# Heater_Driver.net
KiCad netlist of a schematic drawn in Altium Designer
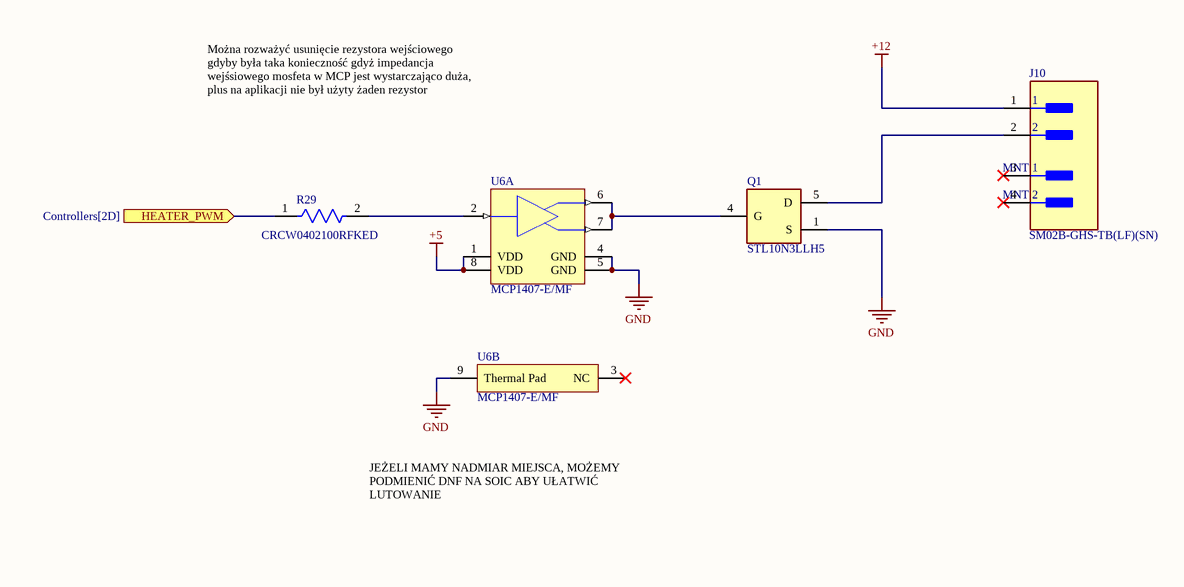
[diagram p0: Heater_Driver.SchDoc]

(export (version "E")
  (design (tool "Eeschema 10.0.6"))
  (components
    (comp (ref "J10")
      (value "SM02B-GHS-TB(LF)(SN)")
      (footprint "FP-SM02B-GHS-TB_LF_SN-MFG")
      (description "CONN HEADER SMD R/A 2POS 1.25MM")
      (libsource (lib "Altium Content Vault") (part "56ec3178a87b3978bdc1b3682cd516a"))
    )
    (comp (ref "Q1")
      (value "STL10N3LLH5")
      (footprint "STL10N3LLH5")
      (description "STMICROELECTRONICS - STL10N3LLH5 - MOSFET, N-CH, 30V, 9A, POWERFLAT")
      (fields (field (name "MOUSER PART NUMBER") "511-STL10N3LLH5"))
      (libsource (lib "STL10N3LLH5") (part "STL10N3LLH5"))
    )
    (comp (ref "R29")
      (value "CRCW0402100RFKED")
      (footprint "FP-CRCW0402-e3-IPC_C")
      (description "RES Thick Film, 100Ω, 1%, 0.063W, 100ppm/°C, 0402")
      (fields (field (name "TOLERANCE") "1%"))
      (libsource (lib "Altium Content Vault") (part "1029c3af85768c4190bb7ad29bc67b5"))
    )
    (comp (ref "U6")
      (value "MCP1407-E/MF")
      (footprint "DFNS-MF8")
      (description "6A High-Speed Power MOSFET Drivers, Non Inverting, Extended Temperature")
      (libsource (lib "Altium Content Vault") (part "IN-MOSDRV-TC4420-9"))
    )
  )
  (nets
    (net (code "1") (name "+5") (class "Default")
      (node (ref "U6") (pin "1") (pinfunction "VDD_1") (pintype "power_in"))
      (node (ref "U6") (pin "8") (pinfunction "VDD_8") (pintype "power_in"))
    )
    (net (code "2") (name "+12") (class "Default")
      (node (ref "J10") (pin "1") (pinfunction "1_1") (pintype "passive"))
    )
    (net (code "3") (name "/HEATER_PWM") (class "Default")
      (node (ref "R29") (pin "1") (pinfunction "1_1") (pintype "passive"))
    )
    (net (code "4") (name "GND") (class "Default")
      (node (ref "Q1") (pin "1") (pinfunction "S_1") (pintype "passive"))
      (node (ref "U6") (pin "4") (pinfunction "GND_4") (pintype "power_in"))
      (node (ref "U6") (pin "5") (pinfunction "GND_5") (pintype "power_in"))
      (node (ref "U6") (pin "9") (pinfunction "Thermal_Pad_9") (pintype "passive"))
    )
    (net (code "5") (name "Net-(Q1-D)") (class "Default")
      (node (ref "J10") (pin "2") (pinfunction "2_2") (pintype "passive"))
      (node (ref "Q1") (pin "5") (pinfunction "D_5") (pintype "passive"))
    )
    (net (code "6") (name "Net-(Q1-G)") (class "Default")
      (node (ref "Q1") (pin "4") (pinfunction "G_4") (pintype "passive"))
      (node (ref "U6") (pin "6") (pinfunction "OUT_6") (pintype "output"))
      (node (ref "U6") (pin "7") (pinfunction "OUT_7") (pintype "output"))
    )
    (net (code "7") (name "Net-(U6A-IN)") (class "Default")
      (node (ref "R29") (pin "2") (pinfunction "2_2") (pintype "passive"))
      (node (ref "U6") (pin "2") (pinfunction "IN_2") (pintype "input"))
    )
    (net (code "8") (name "unconnected-(J10-MNT_1-Pad3)") (class "Default")
      (node (ref "J10") (pin "3") (pinfunction "MNT_1_3") (pintype "passive+no_connect"))
    )
    (net (code "9") (name "unconnected-(J10-MNT_2-Pad4)") (class "Default")
      (node (ref "J10") (pin "4") (pinfunction "MNT_2_4") (pintype "passive+no_connect"))
    )
    (net (code "10") (name "unconnected-(U6B-NC-Pad3)") (class "Default")
      (node (ref "U6") (pin "3") (pinfunction "NC_3") (pintype "passive+no_connect"))
    )
  )
)
